# Display_v4.net
KiCad netlist of a schematic drawn in EAGLE
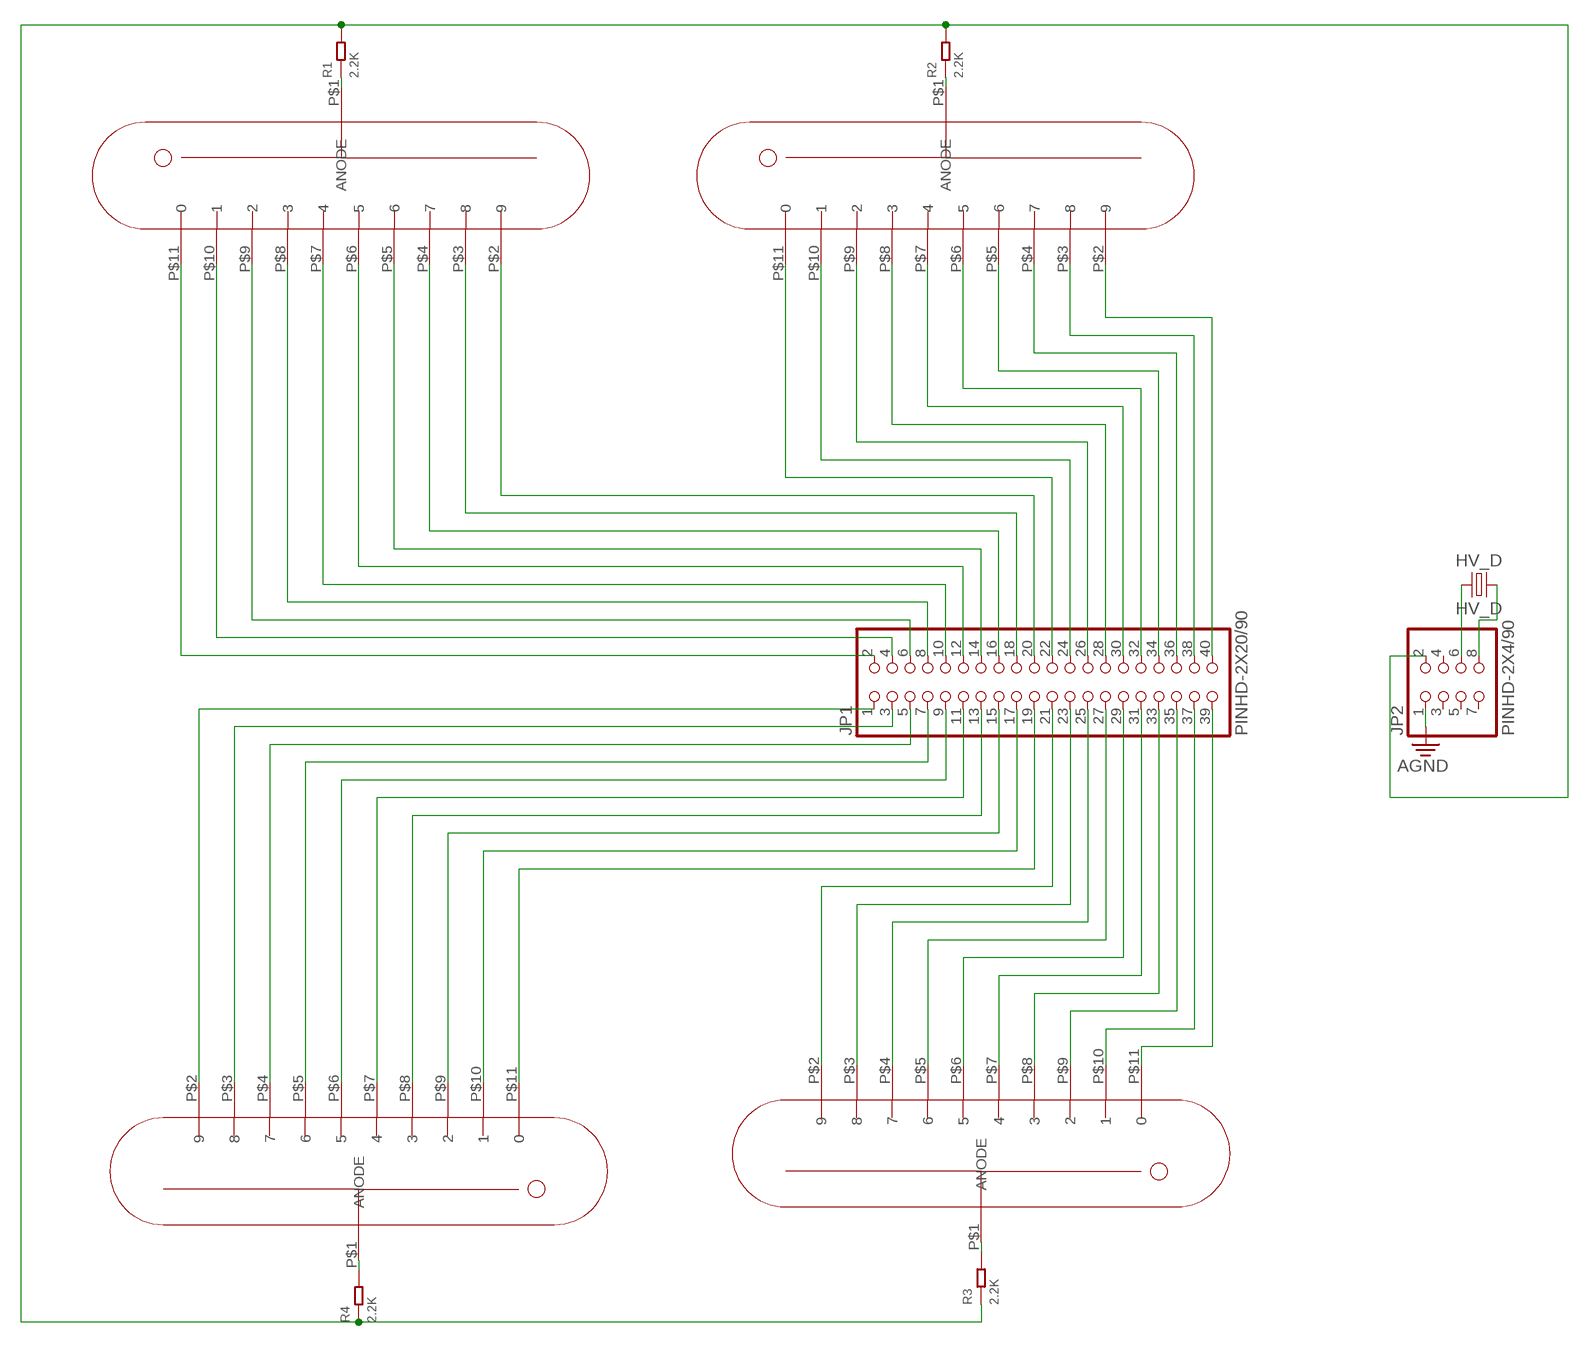
[diagram p0: schematic, sheet 1]

(export (version "E")
  (design (tool "Eeschema 10.0.6"))
  (components
    (comp (ref "HV_D")
      (value "HV_D")
      (footprint "eagle-import:XTALRR488W43L1135T465H1346B")
      (libsource (lib "eagle-import") (part "CRYSTALHC49-11L-13.5H_"))
    )
    (comp (ref "JP1")
      (value "PINHD-2X20/90")
      (footprint "eagle-import:2X20_90")
      (fields (field (name "MANUFACTURER") "Generic"))
      (libsource (lib "eagle-import") (part "PINHD-2X20/90"))
    )
    (comp (ref "JP2")
      (value "PINHD-2X4/90")
      (footprint "eagle-import:2X04_90")
      (fields (field (name "MANUFACTURER") "Generic"))
      (libsource (lib "eagle-import") (part "PINHD-2X4/90"))
    )
    (comp (ref "R1")
      (value "2.2K")
      (footprint "eagle-import:PR-D2.3XL6.5MM")
      (fields (field (name "MPN") "FHCFR-1/4W-222J"))
      (libsource (lib "eagle-import") (part "DIP-RES-2.2K-5%-1/4W(PR-D2.3XL6.5MM)"))
    )
    (comp (ref "R2")
      (value "2.2K")
      (footprint "eagle-import:PR-D2.3XL6.5MM")
      (fields (field (name "MPN") "FHCFR-1/4W-222J"))
      (libsource (lib "eagle-import") (part "DIP-RES-2.2K-5%-1/4W(PR-D2.3XL6.5MM)"))
    )
    (comp (ref "R3")
      (value "2.2K")
      (footprint "eagle-import:PR-D2.3XL6.5MM")
      (fields (field (name "MPN") "FHCFR-1/4W-222J"))
      (libsource (lib "eagle-import") (part "DIP-RES-2.2K-5%-1/4W(PR-D2.3XL6.5MM)"))
    )
    (comp (ref "R4")
      (value "2.2K")
      (footprint "eagle-import:PR-D2.3XL6.5MM")
      (fields (field (name "MPN") "FHCFR-1/4W-222J"))
      (libsource (lib "eagle-import") (part "DIP-RES-2.2K-5%-1/4W(PR-D2.3XL6.5MM)"))
    )
    (comp (ref "U$1")
      (value "IN-12")
      (footprint "eagle-import:IN-12")
      (libsource (lib "eagle-import") (part "IN-12"))
    )
    (comp (ref "U$2")
      (value "IN-12")
      (footprint "eagle-import:IN-12")
      (libsource (lib "eagle-import") (part "IN-12"))
    )
    (comp (ref "U$3")
      (value "IN-12")
      (footprint "eagle-import:IN-12")
      (libsource (lib "eagle-import") (part "IN-12"))
    )
    (comp (ref "U$4")
      (value "IN-12")
      (footprint "eagle-import:IN-12")
      (libsource (lib "eagle-import") (part "IN-12"))
    )
  )
  (nets
    (net (code "1") (name "AGND") (class "Default")
      (node (ref "JP2") (pin "1") (pinfunction "1_1") (pintype "passive"))
    )
    (net (code "2") (name "Net-(HV_D-Pad1)") (class "Default")
      (node (ref "HV_D") (pin "1") (pinfunction "1_1") (pintype "passive"))
      (node (ref "JP2") (pin "6") (pinfunction "6_6") (pintype "passive"))
    )
    (net (code "3") (name "Net-(HV_D-Pad2)") (class "Default")
      (node (ref "HV_D") (pin "2") (pinfunction "2_2") (pintype "passive"))
      (node (ref "JP2") (pin "8") (pinfunction "8_8") (pintype "passive"))
    )
    (net (code "4") (name "Net-(JP2-Pad2)") (class "Default")
      (node (ref "JP2") (pin "2") (pinfunction "2_2") (pintype "passive"))
      (node (ref "R1") (pin "2") (pinfunction "2_2") (pintype "passive"))
      (node (ref "R2") (pin "2") (pinfunction "2_2") (pintype "passive"))
      (node (ref "R3") (pin "1") (pinfunction "1_1") (pintype "passive"))
      (node (ref "R4") (pin "1") (pinfunction "1_1") (pintype "passive"))
    )
    (net (code "5") (name "Net-(U$1-0)") (class "Default")
      (node (ref "JP1") (pin "2") (pinfunction "2_2") (pintype "passive"))
      (node (ref "U$1") (pin "P$11") (pinfunction "0_P$11") (pintype "bidirectional"))
    )
    (net (code "6") (name "Net-(U$1-1)") (class "Default")
      (node (ref "JP1") (pin "4") (pinfunction "4_4") (pintype "passive"))
      (node (ref "U$1") (pin "P$10") (pinfunction "1_P$10") (pintype "bidirectional"))
    )
    (net (code "7") (name "Net-(U$1-2)") (class "Default")
      (node (ref "JP1") (pin "6") (pinfunction "6_6") (pintype "passive"))
      (node (ref "U$1") (pin "P$9") (pinfunction "2_P$9") (pintype "bidirectional"))
    )
    (net (code "8") (name "Net-(U$1-3)") (class "Default")
      (node (ref "JP1") (pin "8") (pinfunction "8_8") (pintype "passive"))
      (node (ref "U$1") (pin "P$8") (pinfunction "3_P$8") (pintype "bidirectional"))
    )
    (net (code "9") (name "Net-(U$1-4)") (class "Default")
      (node (ref "JP1") (pin "10") (pinfunction "10_10") (pintype "passive"))
      (node (ref "U$1") (pin "P$7") (pinfunction "4_P$7") (pintype "bidirectional"))
    )
    (net (code "10") (name "Net-(U$1-5)") (class "Default")
      (node (ref "JP1") (pin "12") (pinfunction "12_12") (pintype "passive"))
      (node (ref "U$1") (pin "P$6") (pinfunction "5_P$6") (pintype "bidirectional"))
    )
    (net (code "11") (name "Net-(U$1-6)") (class "Default")
      (node (ref "JP1") (pin "14") (pinfunction "14_14") (pintype "passive"))
      (node (ref "U$1") (pin "P$5") (pinfunction "6_P$5") (pintype "bidirectional"))
    )
    (net (code "12") (name "Net-(U$1-7)") (class "Default")
      (node (ref "JP1") (pin "16") (pinfunction "16_16") (pintype "passive"))
      (node (ref "U$1") (pin "P$4") (pinfunction "7_P$4") (pintype "bidirectional"))
    )
    (net (code "13") (name "Net-(U$1-8)") (class "Default")
      (node (ref "JP1") (pin "18") (pinfunction "18_18") (pintype "passive"))
      (node (ref "U$1") (pin "P$3") (pinfunction "8_P$3") (pintype "bidirectional"))
    )
    (net (code "14") (name "Net-(U$1-9)") (class "Default")
      (node (ref "JP1") (pin "20") (pinfunction "20_20") (pintype "passive"))
      (node (ref "U$1") (pin "P$2") (pinfunction "9_P$2") (pintype "bidirectional"))
    )
    (net (code "15") (name "Net-(U$1-ANODE)") (class "Default")
      (node (ref "R1") (pin "1") (pinfunction "1_1") (pintype "passive"))
      (node (ref "U$1") (pin "P$1") (pinfunction "ANODE_P$1") (pintype "bidirectional"))
    )
    (net (code "16") (name "Net-(U$2-0)") (class "Default")
      (node (ref "JP1") (pin "22") (pinfunction "22_22") (pintype "passive"))
      (node (ref "U$2") (pin "P$11") (pinfunction "0_P$11") (pintype "bidirectional"))
    )
    (net (code "17") (name "Net-(U$2-1)") (class "Default")
      (node (ref "JP1") (pin "24") (pinfunction "24_24") (pintype "passive"))
      (node (ref "U$2") (pin "P$10") (pinfunction "1_P$10") (pintype "bidirectional"))
    )
    (net (code "18") (name "Net-(U$2-2)") (class "Default")
      (node (ref "JP1") (pin "26") (pinfunction "26_26") (pintype "passive"))
      (node (ref "U$2") (pin "P$9") (pinfunction "2_P$9") (pintype "bidirectional"))
    )
    (net (code "19") (name "Net-(U$2-3)") (class "Default")
      (node (ref "JP1") (pin "28") (pinfunction "28_28") (pintype "passive"))
      (node (ref "U$2") (pin "P$8") (pinfunction "3_P$8") (pintype "bidirectional"))
    )
    (net (code "20") (name "Net-(U$2-4)") (class "Default")
      (node (ref "JP1") (pin "30") (pinfunction "30_30") (pintype "passive"))
      (node (ref "U$2") (pin "P$7") (pinfunction "4_P$7") (pintype "bidirectional"))
    )
    (net (code "21") (name "Net-(U$2-5)") (class "Default")
      (node (ref "JP1") (pin "32") (pinfunction "32_32") (pintype "passive"))
      (node (ref "U$2") (pin "P$6") (pinfunction "5_P$6") (pintype "bidirectional"))
    )
    (net (code "22") (name "Net-(U$2-6)") (class "Default")
      (node (ref "JP1") (pin "34") (pinfunction "34_34") (pintype "passive"))
      (node (ref "U$2") (pin "P$5") (pinfunction "6_P$5") (pintype "bidirectional"))
    )
    (net (code "23") (name "Net-(U$2-7)") (class "Default")
      (node (ref "JP1") (pin "36") (pinfunction "36_36") (pintype "passive"))
      (node (ref "U$2") (pin "P$4") (pinfunction "7_P$4") (pintype "bidirectional"))
    )
    (net (code "24") (name "Net-(U$2-8)") (class "Default")
      (node (ref "JP1") (pin "38") (pinfunction "38_38") (pintype "passive"))
      (node (ref "U$2") (pin "P$3") (pinfunction "8_P$3") (pintype "bidirectional"))
    )
    (net (code "25") (name "Net-(U$2-9)") (class "Default")
      (node (ref "JP1") (pin "40") (pinfunction "40_40") (pintype "passive"))
      (node (ref "U$2") (pin "P$2") (pinfunction "9_P$2") (pintype "bidirectional"))
    )
    (net (code "26") (name "Net-(U$2-ANODE)") (class "Default")
      (node (ref "R2") (pin "1") (pinfunction "1_1") (pintype "passive"))
      (node (ref "U$2") (pin "P$1") (pinfunction "ANODE_P$1") (pintype "bidirectional"))
    )
    (net (code "27") (name "Net-(U$3-0)") (class "Default")
      (node (ref "JP1") (pin "19") (pinfunction "19_19") (pintype "passive"))
      (node (ref "U$3") (pin "P$11") (pinfunction "0_P$11") (pintype "bidirectional"))
    )
    (net (code "28") (name "Net-(U$3-1)") (class "Default")
      (node (ref "JP1") (pin "17") (pinfunction "17_17") (pintype "passive"))
      (node (ref "U$3") (pin "P$10") (pinfunction "1_P$10") (pintype "bidirectional"))
    )
    (net (code "29") (name "Net-(U$3-2)") (class "Default")
      (node (ref "JP1") (pin "15") (pinfunction "15_15") (pintype "passive"))
      (node (ref "U$3") (pin "P$9") (pinfunction "2_P$9") (pintype "bidirectional"))
    )
    (net (code "30") (name "Net-(U$3-3)") (class "Default")
      (node (ref "JP1") (pin "13") (pinfunction "13_13") (pintype "passive"))
      (node (ref "U$3") (pin "P$8") (pinfunction "3_P$8") (pintype "bidirectional"))
    )
    (net (code "31") (name "Net-(U$3-4)") (class "Default")
      (node (ref "JP1") (pin "11") (pinfunction "11_11") (pintype "passive"))
      (node (ref "U$3") (pin "P$7") (pinfunction "4_P$7") (pintype "bidirectional"))
    )
    (net (code "32") (name "Net-(U$3-5)") (class "Default")
      (node (ref "JP1") (pin "9") (pinfunction "9_9") (pintype "passive"))
      (node (ref "U$3") (pin "P$6") (pinfunction "5_P$6") (pintype "bidirectional"))
    )
    (net (code "33") (name "Net-(U$3-6)") (class "Default")
      (node (ref "JP1") (pin "7") (pinfunction "7_7") (pintype "passive"))
      (node (ref "U$3") (pin "P$5") (pinfunction "6_P$5") (pintype "bidirectional"))
    )
    (net (code "34") (name "Net-(U$3-7)") (class "Default")
      (node (ref "JP1") (pin "5") (pinfunction "5_5") (pintype "passive"))
      (node (ref "U$3") (pin "P$4") (pinfunction "7_P$4") (pintype "bidirectional"))
    )
    (net (code "35") (name "Net-(U$3-8)") (class "Default")
      (node (ref "JP1") (pin "3") (pinfunction "3_3") (pintype "passive"))
      (node (ref "U$3") (pin "P$3") (pinfunction "8_P$3") (pintype "bidirectional"))
    )
    (net (code "36") (name "Net-(U$3-9)") (class "Default")
      (node (ref "JP1") (pin "1") (pinfunction "1_1") (pintype "passive"))
      (node (ref "U$3") (pin "P$2") (pinfunction "9_P$2") (pintype "bidirectional"))
    )
    (net (code "37") (name "Net-(U$3-ANODE)") (class "Default")
      (node (ref "R4") (pin "2") (pinfunction "2_2") (pintype "passive"))
      (node (ref "U$3") (pin "P$1") (pinfunction "ANODE_P$1") (pintype "bidirectional"))
    )
    (net (code "38") (name "Net-(U$4-0)") (class "Default")
      (node (ref "JP1") (pin "39") (pinfunction "39_39") (pintype "passive"))
      (node (ref "U$4") (pin "P$11") (pinfunction "0_P$11") (pintype "bidirectional"))
    )
    (net (code "39") (name "Net-(U$4-1)") (class "Default")
      (node (ref "JP1") (pin "37") (pinfunction "37_37") (pintype "passive"))
      (node (ref "U$4") (pin "P$10") (pinfunction "1_P$10") (pintype "bidirectional"))
    )
    (net (code "40") (name "Net-(U$4-2)") (class "Default")
      (node (ref "JP1") (pin "35") (pinfunction "35_35") (pintype "passive"))
      (node (ref "U$4") (pin "P$9") (pinfunction "2_P$9") (pintype "bidirectional"))
    )
    (net (code "41") (name "Net-(U$4-3)") (class "Default")
      (node (ref "JP1") (pin "33") (pinfunction "33_33") (pintype "passive"))
      (node (ref "U$4") (pin "P$8") (pinfunction "3_P$8") (pintype "bidirectional"))
    )
    (net (code "42") (name "Net-(U$4-4)") (class "Default")
      (node (ref "JP1") (pin "31") (pinfunction "31_31") (pintype "passive"))
      (node (ref "U$4") (pin "P$7") (pinfunction "4_P$7") (pintype "bidirectional"))
    )
    (net (code "43") (name "Net-(U$4-5)") (class "Default")
      (node (ref "JP1") (pin "29") (pinfunction "29_29") (pintype "passive"))
      (node (ref "U$4") (pin "P$6") (pinfunction "5_P$6") (pintype "bidirectional"))
    )
    (net (code "44") (name "Net-(U$4-6)") (class "Default")
      (node (ref "JP1") (pin "27") (pinfunction "27_27") (pintype "passive"))
      (node (ref "U$4") (pin "P$5") (pinfunction "6_P$5") (pintype "bidirectional"))
    )
    (net (code "45") (name "Net-(U$4-7)") (class "Default")
      (node (ref "JP1") (pin "25") (pinfunction "25_25") (pintype "passive"))
      (node (ref "U$4") (pin "P$4") (pinfunction "7_P$4") (pintype "bidirectional"))
    )
    (net (code "46") (name "Net-(U$4-8)") (class "Default")
      (node (ref "JP1") (pin "23") (pinfunction "23_23") (pintype "passive"))
      (node (ref "U$4") (pin "P$3") (pinfunction "8_P$3") (pintype "bidirectional"))
    )
    (net (code "47") (name "Net-(U$4-9)") (class "Default")
      (node (ref "JP1") (pin "21") (pinfunction "21_21") (pintype "passive"))
      (node (ref "U$4") (pin "P$2") (pinfunction "9_P$2") (pintype "bidirectional"))
    )
    (net (code "48") (name "Net-(U$4-ANODE)") (class "Default")
      (node (ref "R3") (pin "2") (pinfunction "2_2") (pintype "passive"))
      (node (ref "U$4") (pin "P$1") (pinfunction "ANODE_P$1") (pintype "bidirectional"))
    )
    (net (code "49") (name "unconnected-(JP2-Pad3)") (class "Default")
      (node (ref "JP2") (pin "3") (pinfunction "3_3") (pintype "passive"))
    )
    (net (code "50") (name "unconnected-(JP2-Pad4)") (class "Default")
      (node (ref "JP2") (pin "4") (pinfunction "4_4") (pintype "passive"))
    )
    (net (code "51") (name "unconnected-(JP2-Pad5)") (class "Default")
      (node (ref "JP2") (pin "5") (pinfunction "5_5") (pintype "passive"))
    )
    (net (code "52") (name "unconnected-(JP2-Pad7)") (class "Default")
      (node (ref "JP2") (pin "7") (pinfunction "7_7") (pintype "passive"))
    )
  )
)
